# Isolated-Power-Section.net
KiCad netlist of a schematic drawn in Altium Designer
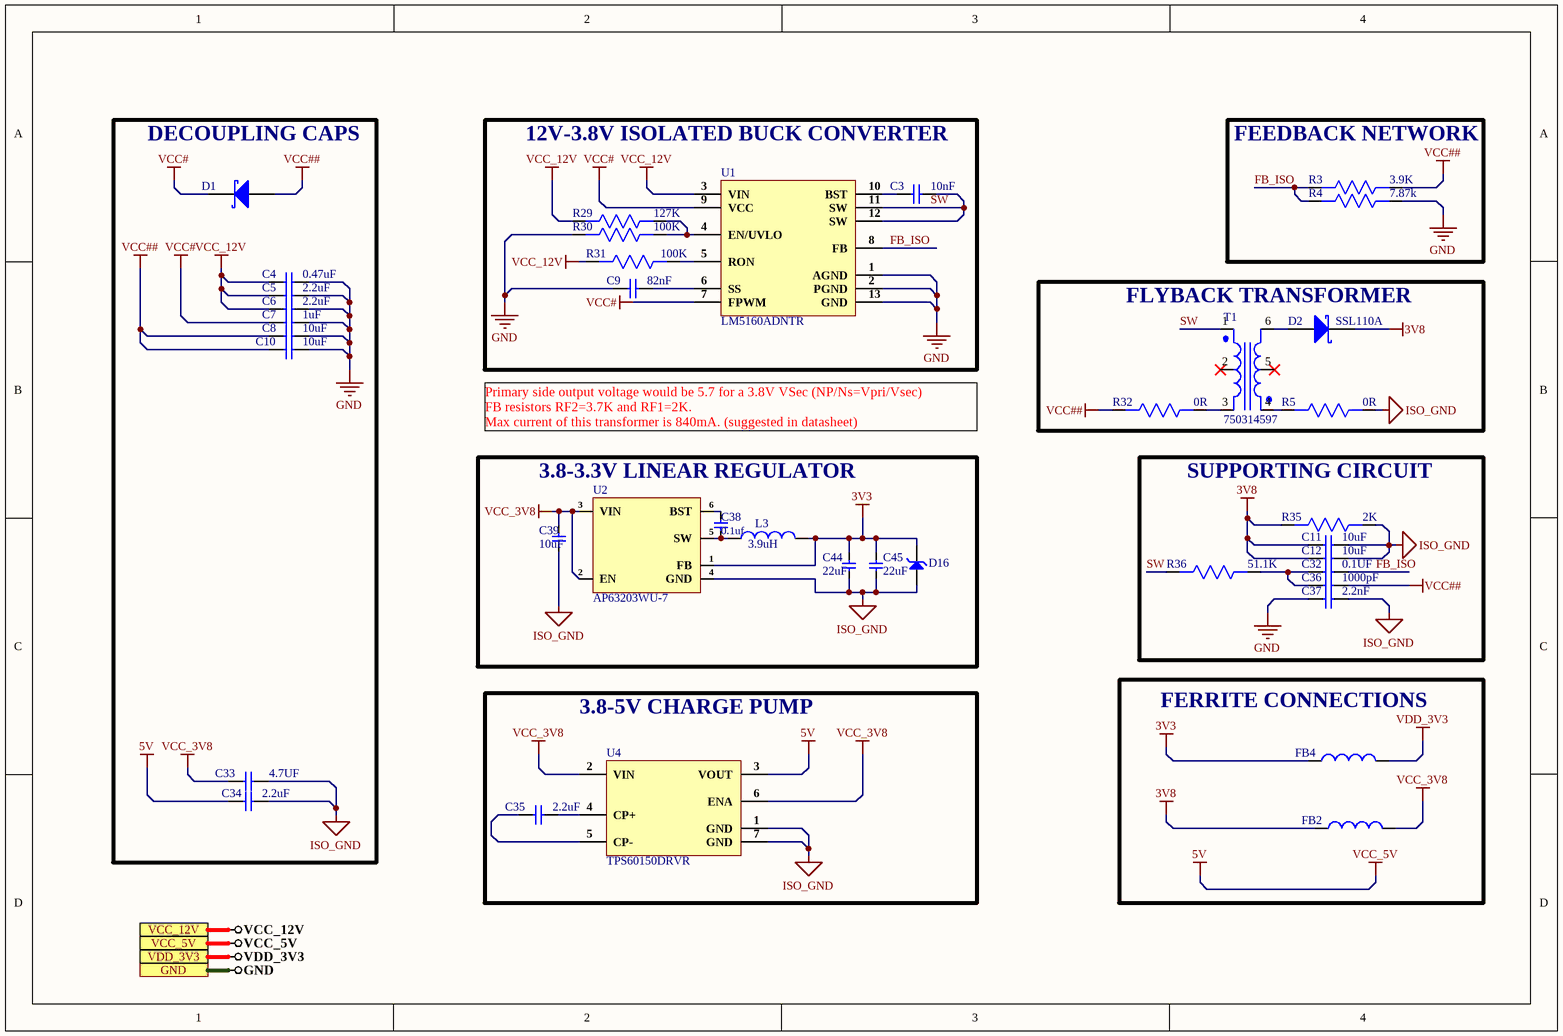
[diagram p0: Isolated-Power-Section.SchDoc]

(export (version "E")
  (design (tool "Eeschema 10.0.6"))
  (components
    (comp (ref "C3")
      (value "10nF")
      (footprint "Cap 0402")
      (description "CAP CER 10000PF 25V X7R 0402")
      (fields
        (field (name "MANUFACTURER") "Yageo")
        (field (name "MANUFACTURER PART NUMBER") "CC0402KRX7R8BB103")
      )
      (libsource (lib "Cole_Benson") (part "CC0402KRX7R8BB103"))
    )
    (comp (ref "C4")
      (value "0.47uF")
      (footprint "Cap 0402")
      (description "CAP CER 0.47UF 50V X5R 0402")
      (fields
        (field (name "MANUFACTURER") "Taiyo Yuden")
        (field (name "MANUFACTURER PART NUMBER") "UMK105ABJ474KV-F")
      )
      (libsource (lib "Cole_Benson") (part "UMK105ABJ474KV-F"))
    )
    (comp (ref "C5")
      (value "2.2uF")
      (footprint "Cap 0603")
      (description "CAP, 2.2µF, 35V, 10%, X5R, 0603")
      (fields
        (field (name "MANUFACTURER") "Murata")
        (field (name "MANUFACTURER PART NUMBER") "GRM188R6YA225KA12D")
      )
      (libsource (lib "Cole_Benson") (part "GRM188R6YA225KA12D"))
    )
    (comp (ref "C6")
      (value "2.2uF")
      (footprint "Cap 0603")
      (description "CAP, 2.2µF, 35V, 10%, X5R, 0603")
      (fields
        (field (name "MANUFACTURER") "Murata")
        (field (name "MANUFACTURER PART NUMBER") "GRM188R6YA225KA12D")
      )
      (libsource (lib "Cole_Benson") (part "GRM188R6YA225KA12D"))
    )
    (comp (ref "C7")
      (value "1uF")
      (footprint "Cap 0603")
      (description "CAP CER 1UF 25V X5R 0603")
      (fields
        (field (name "MANUFACTURER") "Yageo")
        (field (name "MANUFACTURER PART NUMBER") "CC0603KRX5R8BB105")
      )
      (libsource (lib "Cole_Benson") (part "CC0603KRX5R8BB105"))
    )
    (comp (ref "C8")
      (value "10uF")
      (footprint "Cap 0603")
      (description "10uF 35V X5R 20% Pad SMD 0603")
      (fields
        (field (name "MANUFACTURER") "Murata")
        (field (name "MANUFACTURER PART NUMBER") "GRM188R6YA106MA73D")
      )
      (libsource (lib "Cole_Benson") (part "GRM188R6YA106MA73D"))
    )
    (comp (ref "C9")
      (value "82nF")
      (footprint "Cap 0603")
      (description "CAP CER 0.082UF 50V X7R 0603")
      (fields
        (field (name "MANUFACTURER") "Yageo")
        (field (name "MANUFACTURER PART NUMBER") "CC0603KRX7R9BB823")
      )
      (libsource (lib "Cole_Benson") (part "CC0603KRX7R9BB823"))
    )
    (comp (ref "C10")
      (value "10uF")
      (footprint "Cap 0603")
      (description "10uF 35V X5R 20% Pad SMD 0603")
      (fields
        (field (name "MANUFACTURER") "Murata")
        (field (name "MANUFACTURER PART NUMBER") "GRM188R6YA106MA73D")
      )
      (libsource (lib "Cole_Benson") (part "GRM188R6YA106MA73D"))
    )
    (comp (ref "C11")
      (value "10uF")
      (footprint "Cap 0603")
      (description "10uF 35V X5R 20% Pad SMD 0603")
      (fields
        (field (name "MANUFACTURER") "Murata")
        (field (name "MANUFACTURER PART NUMBER") "GRM188R6YA106MA73D")
      )
      (libsource (lib "Cole_Benson") (part "GRM188R6YA106MA73D"))
    )
    (comp (ref "C12")
      (value "10uF")
      (footprint "Cap 0603")
      (description "10uF 35V X5R 20% Pad SMD 0603")
      (fields
        (field (name "MANUFACTURER") "Murata")
        (field (name "MANUFACTURER PART NUMBER") "GRM188R6YA106MA73D")
      )
      (libsource (lib "Cole_Benson") (part "GRM188R6YA106MA73D"))
    )
    (comp (ref "C32")
      (value "0.1UF")
      (footprint "Cap 0402")
      (description "CAP CER 0.1UF 50V X7R 0402")
      (fields
        (field (name "MANUFACTURER") "Samsung")
        (field (name "MANUFACTURER PART NUMBER") "CL05B104KB54PNC")
      )
      (libsource (lib "Cole_Benson") (part "CL05B104KB54PNC"))
    )
    (comp (ref "C33")
      (value "4.7UF")
      (footprint "Cap 0603")
      (description "CAP CER 4.7UF 25V X5R 0603")
      (fields
        (field (name "MANUFACTURER") "Samsung")
        (field (name "MANUFACTURER PART NUMBER") "CL10A475KA8NQNC")
      )
      (libsource (lib "Cole_Benson") (part "CL10A475KA8NQNC"))
    )
    (comp (ref "C34")
      (value "2.2uF")
      (footprint "Cap 0603")
      (description "CAP, 2.2µF, 35V, 10%, X5R, 0603")
      (fields
        (field (name "MANUFACTURER") "Murata")
        (field (name "MANUFACTURER PART NUMBER") "GRM188R6YA225KA12D")
      )
      (libsource (lib "Cole_Benson") (part "GRM188R6YA225KA12D"))
    )
    (comp (ref "C35")
      (value "2.2uF")
      (footprint "Cap 0603")
      (description "CAP, 2.2µF, 35V, 10%, X5R, 0603")
      (fields
        (field (name "MANUFACTURER") "Murata")
        (field (name "MANUFACTURER PART NUMBER") "GRM188R6YA225KA12D")
      )
      (libsource (lib "Cole_Benson") (part "GRM188R6YA225KA12D"))
    )
    (comp (ref "C36")
      (value "1000pF")
      (footprint "Cap 0402")
      (description "CAP CER 1000PF 100V X7R 0402")
      (fields
        (field (name "MANUFACTURER") "Wurth Electronics")
        (field (name "MANUFACTURER PART NUMBER") "885012205080")
      )
      (libsource (lib "Cole_Benson") (part "885012205080"))
    )
    (comp (ref "C37")
      (value "2.2nF")
      (footprint "Cap 0603")
      (description "CAP CER 2200PF 50V X7R 0603")
      (fields
        (field (name "MANUFACTURER") "Yageo")
        (field (name "MANUFACTURER PART NUMBER") "CC0603KRX7R9BB222")
      )
      (libsource (lib "Cole_Benson") (part "CC0603KRX7R9BB222"))
    )
    (comp (ref "C38")
      (value "0.1uf")
      (footprint "Cap-0402")
      (description "CAP CER 0.1UF 100V X5R 0402")
      (fields
        (field (name "MANUFACTURER") "Murata")
        (field (name "MANUFACTURER PART NUMBER") "GRM155R62A104KE14D")
      )
      (libsource (lib "eSpark Libraries") (part "GRM155R62A104KE14D"))
    )
    (comp (ref "C39")
      (value "10uF")
      (footprint "Cap-0603")
      (description "CAP CER 10UF 25V X5R 0603")
      (fields
        (field (name "MANUFACTURER") "TDK")
        (field (name "MANUFACTURER PART NUMBER") "C1608X5R1E106M080AC")
      )
      (libsource (lib "eSpark Libraries") (part "C1608X5R1E106M080AC"))
    )
    (comp (ref "C44")
      (value "22uF")
      (footprint "Cap-0805")
      (description "CAP CER 22UF 35V X5R 0805")
      (fields
        (field (name "MANUFACTURER") "TDK Corporation")
        (field (name "MANUFACTURER PART NUMBER") "C2012X5R1V226MT000E")
      )
      (libsource (lib "eSpark Libraries") (part "C2012X5R1V226MT000E"))
    )
    (comp (ref "C45")
      (value "22uF")
      (footprint "Cap-0805")
      (description "CAP CER 22UF 35V X5R 0805")
      (fields
        (field (name "MANUFACTURER") "TDK Corporation")
        (field (name "MANUFACTURER PART NUMBER") "C2012X5R1V226MT000E")
      )
      (libsource (lib "eSpark Libraries") (part "C2012X5R1V226MT000E"))
    )
    (comp (ref "D1")
      (value "CUS10S30,H3F")
      (footprint "CUS10S30,H3F")
      (description "Diode Schottky 30V 1A Surface Mount USC")
      (fields (field (name "MANUFACTURER") "Toshiba"))
      (libsource (lib "Cole_Benson") (part "CUS10S30,H3F"))
    )
    (comp (ref "D2")
      (value "SSL110A")
      (footprint "SMA")
      (description "500μA@100V 100V Single 600mV@1A 1A SMA Schottky Barrier Diodes (SBD) ROHS")
      (fields (field (name "MANUFACTURER") "Yangzhou"))
      (libsource (lib "Cole_Benson") (part "SSL110A"))
    )
    (comp (ref "D16")
      (value "MSP3V3HM3/89A")
      (footprint "MicroSMP")
      (description "TVS DIODE 3.3VWM 11.5VC MICROSMP")
      (fields (field (name "LCSC PART NUMBER") "C241899"))
      (libsource (lib "Cole_Benson") (part "MSP3V3HM3/89A"))
    )
    (comp (ref "FB2")
      (value "MPZ1608S121ATDH5")
      (footprint "MPZ1608S121ATDH5")
      (description "Ferrite Beads Multi-Layer 120Ohm 25% 100MHz 2A 45mOhm DCR 0603 Automotive T/R")
      (fields (field (name "MANUFACTURER") "TDK") (field (name "TOLERANCE") "25%"))
      (libsource (lib "Cole_Benson") (part "MPZ1608S121ATDH5"))
    )
    (comp (ref "FB4")
      (value "MPZ1608S121ATDH5")
      (footprint "MPZ1608S121ATDH5")
      (description "Ferrite Beads Multi-Layer 120Ohm 25% 100MHz 2A 45mOhm DCR 0603 Automotive T/R")
      (fields (field (name "MANUFACTURER") "TDK") (field (name "TOLERANCE") "25%"))
      (libsource (lib "Cole_Benson") (part "MPZ1608S121ATDH5"))
    )
    (comp (ref "L3")
      (value "3.9uH")
      (footprint "FNR3015S3R9MT")
      (description "1.5A 3.9uH ±20% 1.4A SMD,3x3mm Power Inductors ROHS")
      (fields
        (field (name "MANUFACTURER") "cjiang")
        (field (name "MANUFACTURER PART NUMBER") "FNR3015S3R9MT")
      )
      (libsource (lib "Cole_Benson") (part "FNR3015S3R9MT"))
    )
    (comp (ref "R3")
      (value "3.9K")
      (footprint "Res0603")
      (description "Res 0603 3.9K Ohm 1% 0.1W(1/10W) ±100ppm/°C Pad SMD T/R")
      (fields
        (field (name "MANUFACTURER") "Yageo")
        (field (name "MANUFACTURER PART NUMBER") "RC0603FR-073K9L")
      )
      (libsource (lib "Cole_Benson") (part "RC0603FR-073K9L"))
    )
    (comp (ref "R4")
      (value "7.87k")
      (footprint "Res0603")
      (description "100mW 50V ±1% ±100ppm/℃ -55℃~+155℃ 7.87kΩ 0603 Chip Resistor - Surface Mount ROHS")
      (fields (field (name "MANUFACTURER") "FH") (field (name "MANUFACTURER PART NUMBER") "RS-03K7871FT"))
      (libsource (lib "Cole_Benson") (part "RS-03K7871FT"))
    )
    (comp (ref "R5")
      (value "0R")
      (footprint "Res0603")
      (description "RES SMD 0R, 1%, 0.1W, 0603")
      (fields
        (field (name "MANUFACTURER") "Yageo")
        (field (name "MANUFACTURER PART NUMBER") "RC0603FR-070RL")
      )
      (libsource (lib "Cole_Benson") (part "RC0603FR-070RL"))
    )
    (comp (ref "R29")
      (value "127K")
      (footprint "Res0603")
      (description "RES SMD 127K OHM 1% 1/10W 0603")
      (fields
        (field (name "MANUFACTURER") "Yageo")
        (field (name "MANUFACTURER PART NUMBER") "RT0603FRE07127KL")
      )
      (libsource (lib "Cole_Benson") (part "RT0603FRE07127KL"))
    )
    (comp (ref "R30")
      (value "100K")
      (footprint "Res0603")
      (description "Res Thick Film 0603 100K Ohm 5% 1/10W 100ppm/C Molded SMD SMD Paper T/R")
      (fields
        (field (name "MANUFACTURER") "Yageo")
        (field (name "MANUFACTURER PART NUMBER") "RC0603JR-07100KL")
      )
      (libsource (lib "Cole_Benson") (part "RC0603JR-07100KL"))
    )
    (comp (ref "R31")
      (value "100K")
      (footprint "Res0603")
      (description "Res Thick Film 0603 100K Ohm 5% 1/10W 100ppm/C Molded SMD SMD Paper T/R")
      (fields
        (field (name "MANUFACTURER") "Yageo")
        (field (name "MANUFACTURER PART NUMBER") "RC0603JR-07100KL")
      )
      (libsource (lib "Cole_Benson") (part "RC0603JR-07100KL"))
    )
    (comp (ref "R32")
      (value "0R")
      (footprint "Res0603")
      (description "RES SMD 0R, 1%, 0.1W, 0603")
      (fields
        (field (name "MANUFACTURER") "Yageo")
        (field (name "MANUFACTURER PART NUMBER") "RC0603FR-070RL")
      )
      (libsource (lib "Cole_Benson") (part "RC0603FR-070RL"))
    )
    (comp (ref "R35")
      (value "2K")
      (footprint "Res0603")
      (description "RES SMD 2K OHM 1% 1/10W 0603")
      (fields
        (field (name "MANUFACTURER") "Yageo")
        (field (name "MANUFACTURER PART NUMBER") "RC0603FR-072KL")
      )
      (libsource (lib "Cole_Benson") (part "RC0603FR-072KL"))
    )
    (comp (ref "R36")
      (value "51.1K")
      (footprint "Res0603")
      (description "Res SMD 0603 51.1K Ohm 0.1% 1/10W")
      (fields
        (field (name "MANUFACTURER") "Panasonic")
        (field (name "MANUFACTURER PART NUMBER") "ERA-3AEB5112V")
      )
      (libsource (lib "Cole_Benson") (part "ERA3AEB5112V"))
    )
    (comp (ref "T1")
      (value "750314597")
      (footprint "750314597")
      (description "XFRMR ISOL BUCK DC/DC CONV SMD")
      (fields (field (name "MANUFACTURER") "Wurth Electronics Midcom"))
      (libsource (lib "Cole_Benson") (part "750314597"))
    )
    (comp (ref "U1")
      (value "LM5160ADNTR")
      (footprint "LM5160ADNTR")
      (description "IC REG BUCK FLYBCK ADJ 12WSON")
      (fields (field (name "MANUFACTURER") "Texas Instruments"))
      (libsource (lib "Cole_Benson") (part "LM5160ADNTR"))
    )
    (comp (ref "U2")
      (value "AP63203WU-7")
      (footprint "TSOT-23-6")
      (description "IC REG BUCK 3.3V 2A TSOT26")
      (fields (field (name "MANUFACTURER") "Diodes") (field (name "LCSC PART NUMBER") "C780769"))
      (libsource (lib "eSpark Libraries") (part "AP63203WU-7"))
    )
    (comp (ref "U4")
      (value "TPS60150DRVR")
      (footprint "TPS60150DRVR")
      (description "IC REG CHARGE PUMP 5V 140MA 6SON")
      (fields (field (name "MANUFACTURER") "Texas Instruments"))
      (libsource (lib "Cole_Benson") (part "TPS60150DRVR"))
    )
  )
  (nets
    (net (code "1") (name "/FB_ISO") (class "Default")
      (node (ref "C32") (pin "2") (pinfunction "2_2") (pintype "passive"))
      (node (ref "R3") (pin "2") (pintype "passive"))
      (node (ref "R4") (pin "2") (pintype "passive"))
      (node (ref "U1") (pin "8") (pinfunction "FB_8") (pintype "passive"))
    )
    (net (code "2") (name "/SW") (class "Default")
      (node (ref "C3") (pin "2") (pinfunction "2_2") (pintype "passive"))
      (node (ref "R36") (pin "2") (pintype "passive"))
      (node (ref "T1") (pin "1") (pinfunction "PRI_1_1") (pintype "passive"))
      (node (ref "U1") (pin "11") (pinfunction "SW_11") (pintype "passive"))
      (node (ref "U1") (pin "12") (pinfunction "SW_12") (pintype "passive"))
    )
    (net (code "3") (name "3V3") (class "Default")
      (node (ref "C44") (pin "2") (pinfunction "2_2") (pintype "passive"))
      (node (ref "C45") (pin "2") (pinfunction "2_2") (pintype "passive"))
      (node (ref "D16") (pin "2") (pinfunction "K_2") (pintype "passive"))
      (node (ref "FB4") (pin "1") (pinfunction "1_1") (pintype "passive"))
      (node (ref "L3") (pin "2") (pinfunction "2_2") (pintype "passive"))
      (node (ref "U2") (pin "1") (pinfunction "FB_1") (pintype "passive"))
    )
    (net (code "4") (name "3V8") (class "Default")
      (node (ref "C11") (pin "1") (pinfunction "1_1") (pintype "passive"))
      (node (ref "C12") (pin "1") (pinfunction "1_1") (pintype "passive"))
      (node (ref "D2") (pin "1") (pinfunction "K_1") (pintype "passive"))
      (node (ref "FB2") (pin "1") (pinfunction "1_1") (pintype "passive"))
      (node (ref "R35") (pin "2") (pintype "passive"))
    )
    (net (code "5") (name "5V") (class "Default")
      (node (ref "C34") (pin "1") (pinfunction "1_1") (pintype "passive"))
      (node (ref "U4") (pin "3") (pinfunction "VOUT_3") (pintype "passive"))
    )
    (net (code "6") (name "GND") (class "Default")
      (node (ref "C10") (pin "2") (pinfunction "2_2") (pintype "passive"))
      (node (ref "C37") (pin "1") (pinfunction "1_1") (pintype "passive"))
      (node (ref "C4") (pin "2") (pinfunction "2_2") (pintype "passive"))
      (node (ref "C5") (pin "2") (pinfunction "2_2") (pintype "passive"))
      (node (ref "C6") (pin "2") (pinfunction "2_2") (pintype "passive"))
      (node (ref "C7") (pin "2") (pinfunction "2_2") (pintype "passive"))
      (node (ref "C8") (pin "2") (pinfunction "2_2") (pintype "passive"))
      (node (ref "C9") (pin "1") (pinfunction "1_1") (pintype "passive"))
      (node (ref "R30") (pin "2") (pintype "passive"))
      (node (ref "R4") (pin "1") (pintype "passive"))
      (node (ref "U1") (pin "1") (pinfunction "AGND_1") (pintype "passive"))
      (node (ref "U1") (pin "13") (pinfunction "GND_13") (pintype "passive"))
      (node (ref "U1") (pin "2") (pinfunction "PGND_2") (pintype "passive"))
    )
    (net (code "7") (name "ISO_GND") (class "Default")
      (node (ref "C11") (pin "2") (pinfunction "2_2") (pintype "passive"))
      (node (ref "C12") (pin "2") (pinfunction "2_2") (pintype "passive"))
      (node (ref "C33") (pin "2") (pinfunction "2_2") (pintype "passive"))
      (node (ref "C34") (pin "2") (pinfunction "2_2") (pintype "passive"))
      (node (ref "C37") (pin "2") (pinfunction "2_2") (pintype "passive"))
      (node (ref "C39") (pin "1") (pinfunction "1_1") (pintype "passive"))
      (node (ref "C44") (pin "1") (pinfunction "1_1") (pintype "passive"))
      (node (ref "C45") (pin "1") (pinfunction "1_1") (pintype "passive"))
      (node (ref "D16") (pin "1") (pinfunction "A_1") (pintype "passive"))
      (node (ref "R35") (pin "1") (pintype "passive"))
      (node (ref "R5") (pin "1") (pintype "passive"))
      (node (ref "U2") (pin "4") (pinfunction "GND_4") (pintype "passive"))
      (node (ref "U4") (pin "1") (pinfunction "GND_1") (pintype "passive"))
      (node (ref "U4") (pin "7") (pinfunction "GND_7") (pintype "passive"))
    )
    (net (code "8") (name "Net-(C32-Pad1)") (class "Default")
      (node (ref "C32") (pin "1") (pinfunction "1_1") (pintype "passive"))
      (node (ref "C36") (pin "1") (pinfunction "1_1") (pintype "passive"))
      (node (ref "R36") (pin "1") (pintype "passive"))
    )
    (net (code "9") (name "Net-(D2-A)") (class "Default")
      (node (ref "D2") (pin "2") (pinfunction "A_2") (pintype "passive"))
      (node (ref "T1") (pin "6") (pinfunction "SEC_2_6") (pintype "passive"))
    )
    (net (code "10") (name "Net-(T1-PRI_2)") (class "Default")
      (node (ref "R32") (pin "1") (pintype "passive"))
      (node (ref "T1") (pin "3") (pinfunction "PRI_2_3") (pintype "passive"))
    )
    (net (code "11") (name "Net-(T1-SEC_1)") (class "Default")
      (node (ref "R5") (pin "2") (pintype "passive"))
      (node (ref "T1") (pin "4") (pinfunction "SEC_1_4") (pintype "passive"))
    )
    (net (code "12") (name "Net-(U1-BST)") (class "Default")
      (node (ref "C3") (pin "1") (pinfunction "1_1") (pintype "passive"))
      (node (ref "U1") (pin "10") (pinfunction "BST_10") (pintype "passive"))
    )
    (net (code "13") (name "Net-(U1-EN{slash}UVLO)") (class "Default")
      (node (ref "R29") (pin "1") (pintype "passive"))
      (node (ref "R30") (pin "1") (pintype "passive"))
      (node (ref "U1") (pin "4") (pinfunction "EN/UVLO_4") (pintype "passive"))
    )
    (net (code "14") (name "Net-(U1-RON)") (class "Default")
      (node (ref "R31") (pin "1") (pintype "passive"))
      (node (ref "U1") (pin "5") (pinfunction "RON_5") (pintype "passive"))
    )
    (net (code "15") (name "Net-(U1-SS)") (class "Default")
      (node (ref "C9") (pin "2") (pinfunction "2_2") (pintype "passive"))
      (node (ref "U1") (pin "6") (pinfunction "SS_6") (pintype "passive"))
    )
    (net (code "16") (name "Net-(U2-BST)") (class "Default")
      (node (ref "C38") (pin "2") (pinfunction "2_2") (pintype "passive"))
      (node (ref "U2") (pin "6") (pinfunction "BST_6") (pintype "passive"))
    )
    (net (code "17") (name "Net-(U2-SW)") (class "Default")
      (node (ref "C38") (pin "1") (pinfunction "1_1") (pintype "passive"))
      (node (ref "L3") (pin "1") (pinfunction "1_1") (pintype "passive"))
      (node (ref "U2") (pin "5") (pinfunction "SW_5") (pintype "passive"))
    )
    (net (code "18") (name "Net-(U4-CP+)") (class "Default")
      (node (ref "C35") (pin "2") (pinfunction "2_2") (pintype "passive"))
      (node (ref "U4") (pin "4") (pinfunction "CP+_4") (pintype "passive"))
    )
    (net (code "19") (name "Net-(U4-CP-)") (class "Default")
      (node (ref "C35") (pin "1") (pinfunction "1_1") (pintype "passive"))
      (node (ref "U4") (pin "5") (pinfunction "CP-_5") (pintype "passive"))
    )
    (net (code "20") (name "VCC#") (class "Default")
      (node (ref "C7") (pin "1") (pinfunction "1_1") (pintype "passive"))
      (node (ref "D1") (pin "1") (pinfunction "K_1") (pintype "passive"))
      (node (ref "U1") (pin "7") (pinfunction "FPWM_7") (pintype "passive"))
      (node (ref "U1") (pin "9") (pinfunction "VCC_9") (pintype "passive"))
    )
    (net (code "21") (name "VCC##") (class "Default")
      (node (ref "C10") (pin "1") (pinfunction "1_1") (pintype "passive"))
      (node (ref "C36") (pin "2") (pinfunction "2_2") (pintype "passive"))
      (node (ref "C8") (pin "1") (pinfunction "1_1") (pintype "passive"))
      (node (ref "D1") (pin "2") (pinfunction "A_2") (pintype "passive"))
      (node (ref "R3") (pin "1") (pintype "passive"))
      (node (ref "R32") (pin "2") (pintype "passive"))
    )
    (net (code "22") (name "VCC_3V8") (class "Default")
      (node (ref "C33") (pin "1") (pinfunction "1_1") (pintype "passive"))
      (node (ref "C39") (pin "2") (pinfunction "2_2") (pintype "passive"))
      (node (ref "FB2") (pin "2") (pinfunction "2_2") (pintype "passive"))
      (node (ref "U2") (pin "2") (pinfunction "EN_2") (pintype "passive"))
      (node (ref "U2") (pin "3") (pinfunction "VIN_3") (pintype "passive"))
      (node (ref "U4") (pin "2") (pinfunction "VIN_2") (pintype "passive"))
      (node (ref "U4") (pin "6") (pinfunction "ENA_6") (pintype "passive"))
    )
    (net (code "23") (name "VCC_12V") (class "Default")
      (node (ref "C4") (pin "1") (pinfunction "1_1") (pintype "passive"))
      (node (ref "C5") (pin "1") (pinfunction "1_1") (pintype "passive"))
      (node (ref "C6") (pin "1") (pinfunction "1_1") (pintype "passive"))
      (node (ref "R29") (pin "2") (pintype "passive"))
      (node (ref "R31") (pin "2") (pintype "passive"))
      (node (ref "U1") (pin "3") (pinfunction "VIN_3") (pintype "passive"))
    )
    (net (code "24") (name "VDD_3V3") (class "Default")
      (node (ref "FB4") (pin "2") (pinfunction "2_2") (pintype "passive"))
    )
    (net (code "25") (name "unconnected-(T1-NC-Pad2)") (class "Default")
      (node (ref "T1") (pin "2") (pinfunction "NC_2") (pintype "passive+no_connect"))
    )
    (net (code "26") (name "unconnected-(T1-NC-Pad5)") (class "Default")
      (node (ref "T1") (pin "5") (pinfunction "NC_5") (pintype "passive+no_connect"))
    )
  )
)
